# Sheet1.net
KiCad netlist of a schematic drawn in Altium Designer
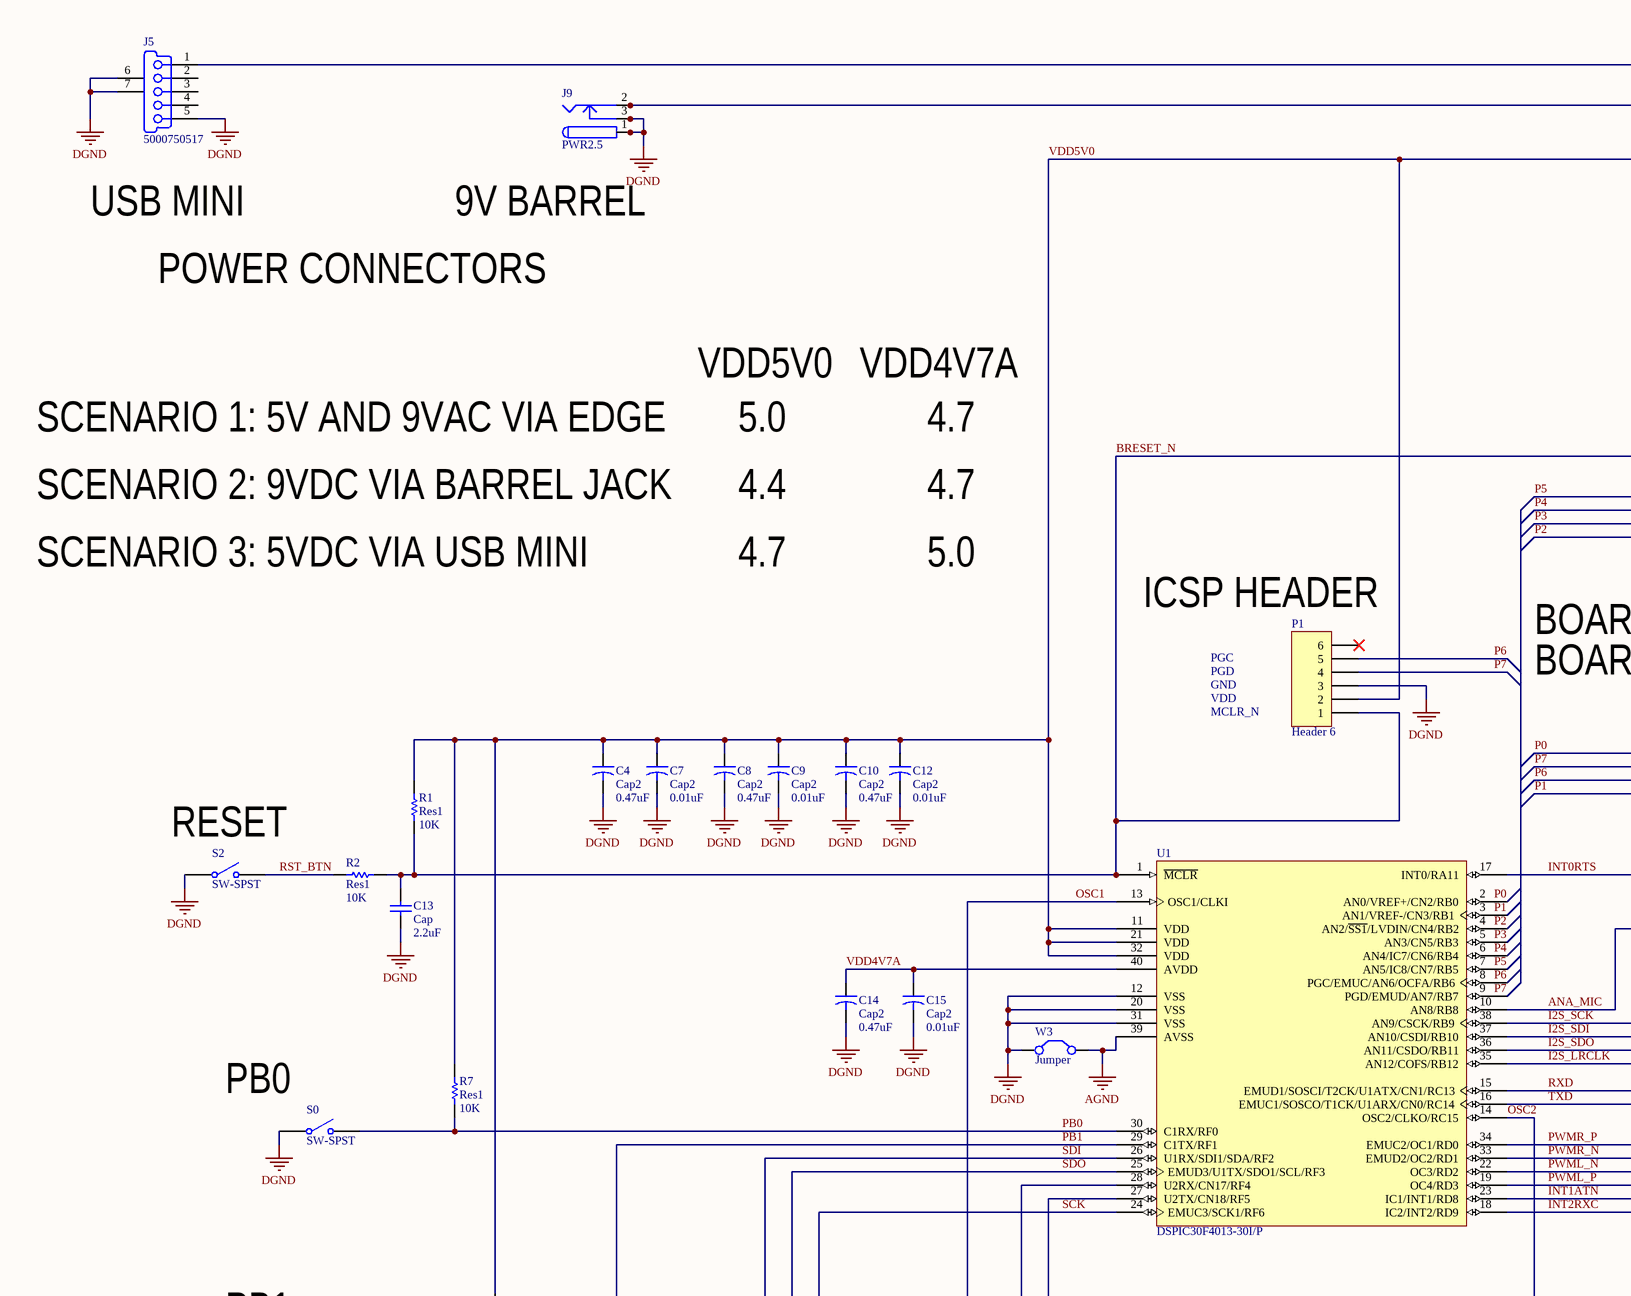
[diagram p0: Sheet1.SchDoc, top left]
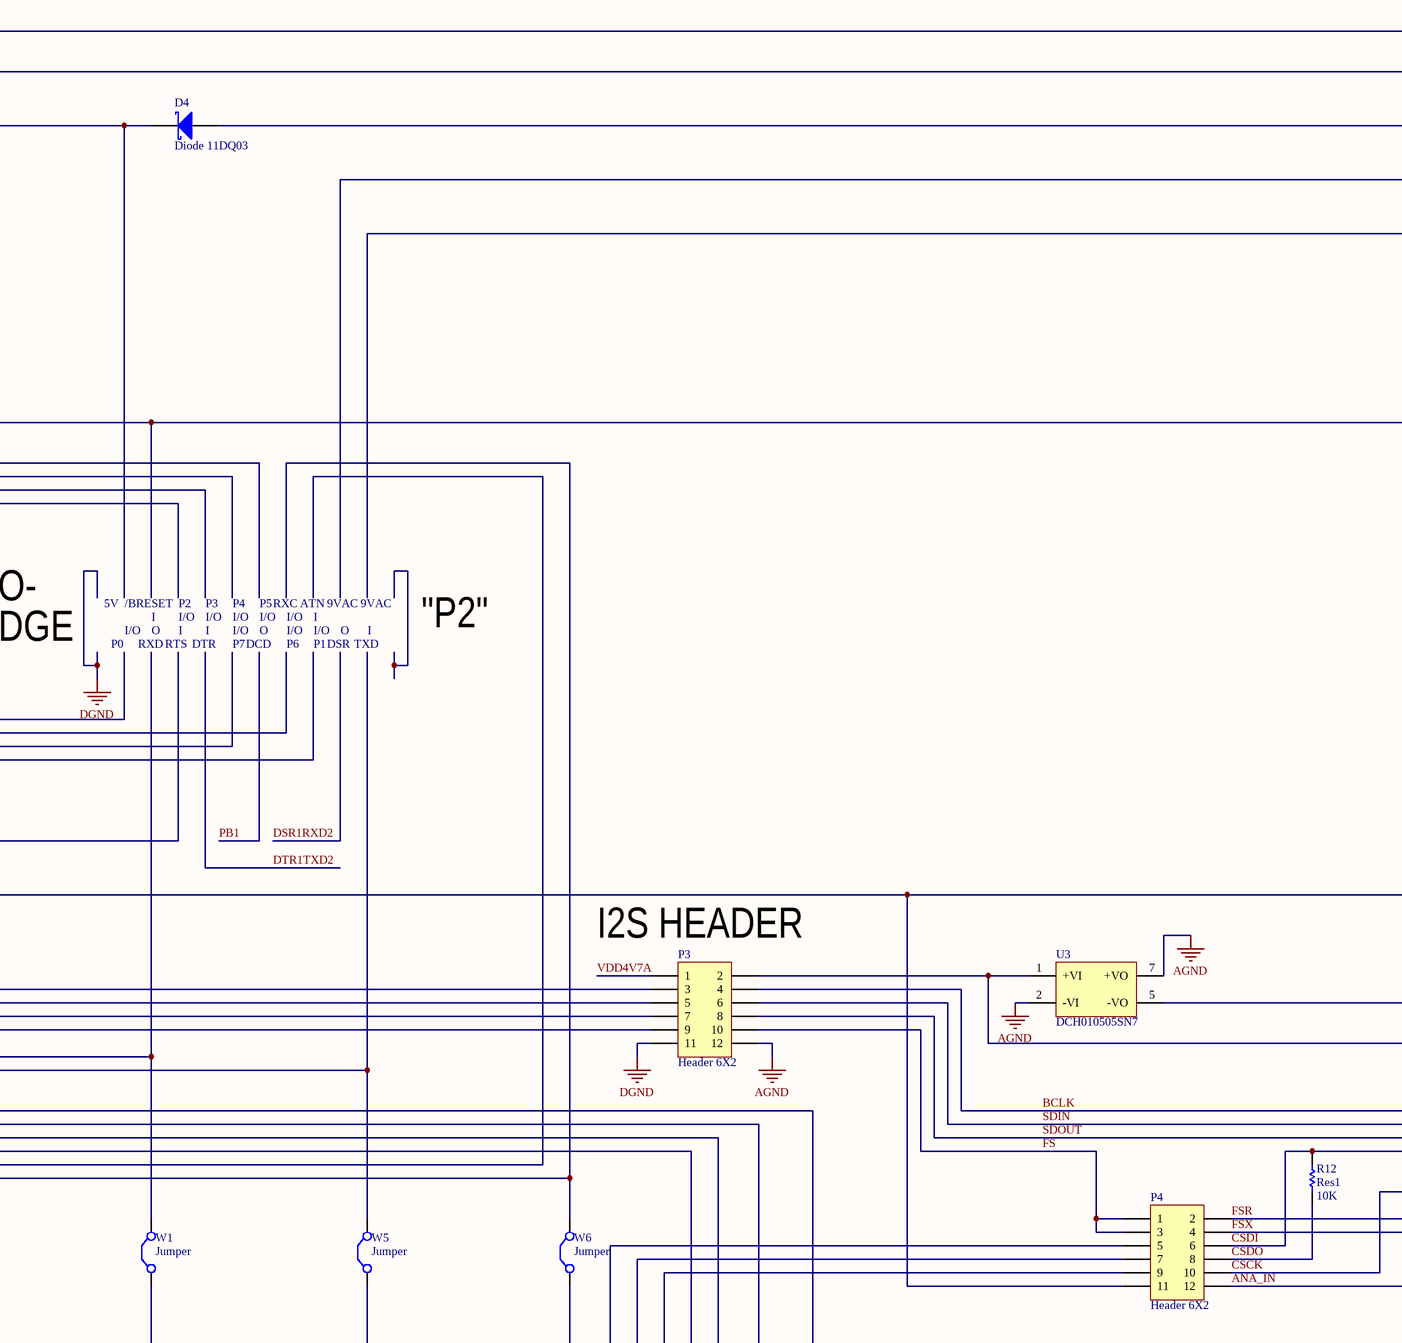
[diagram p1: Sheet1.SchDoc, top middle]
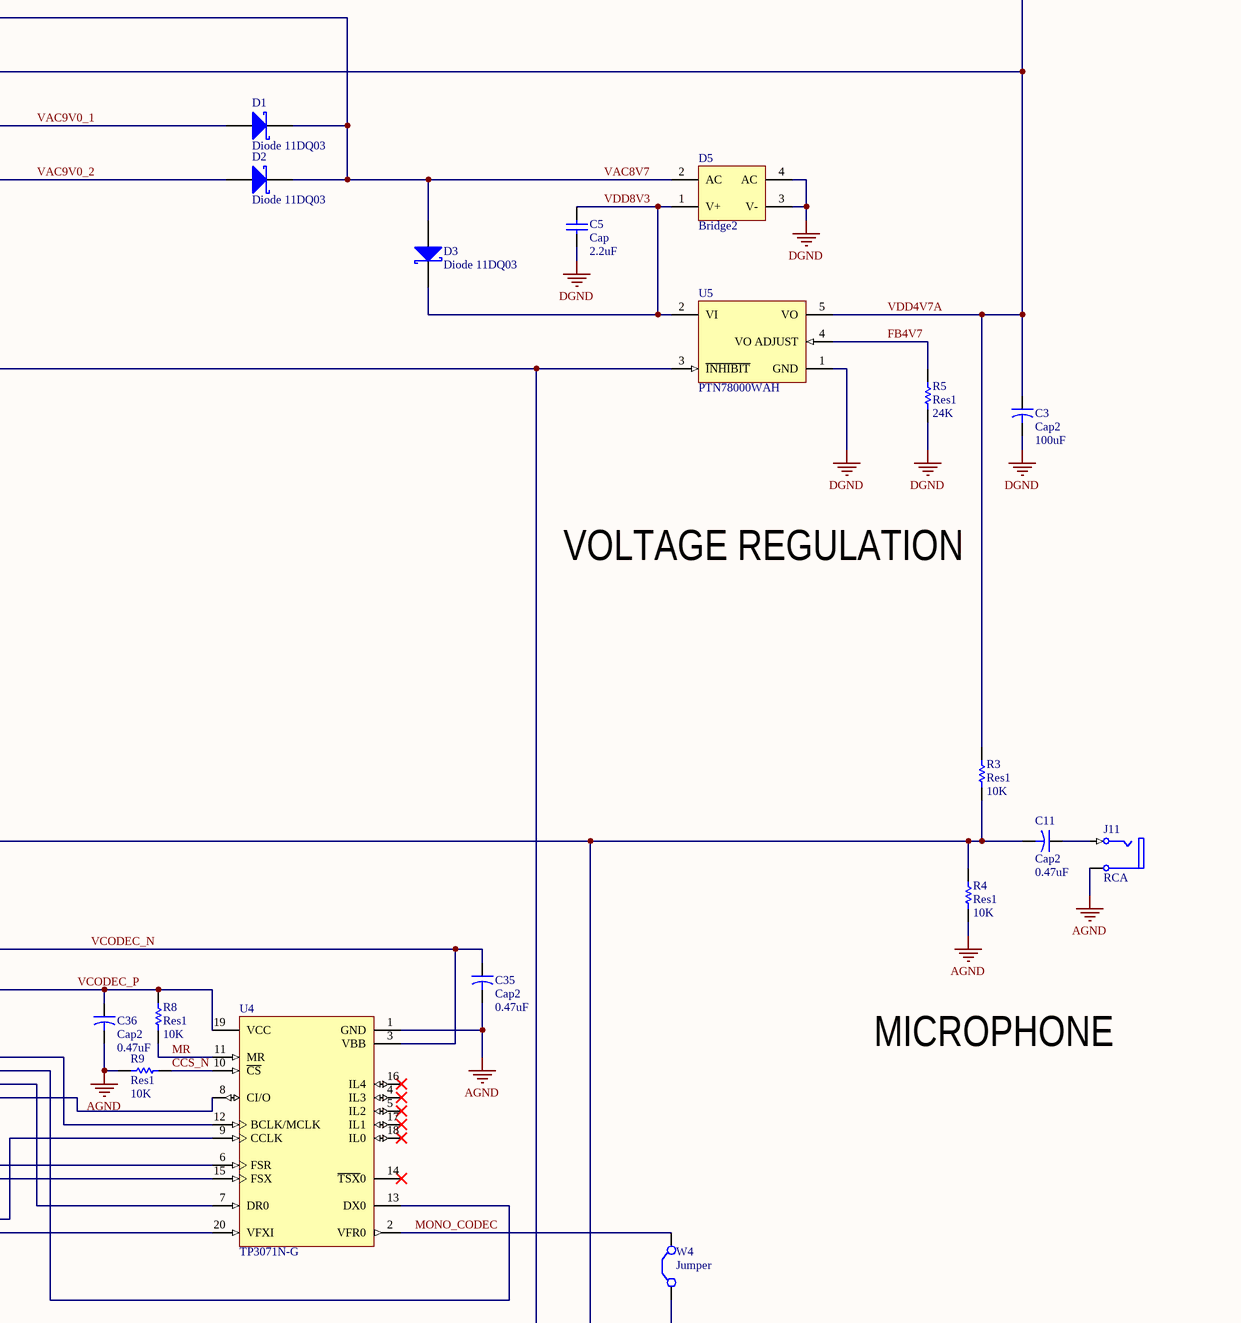
[diagram p2: Sheet1.SchDoc, top right]
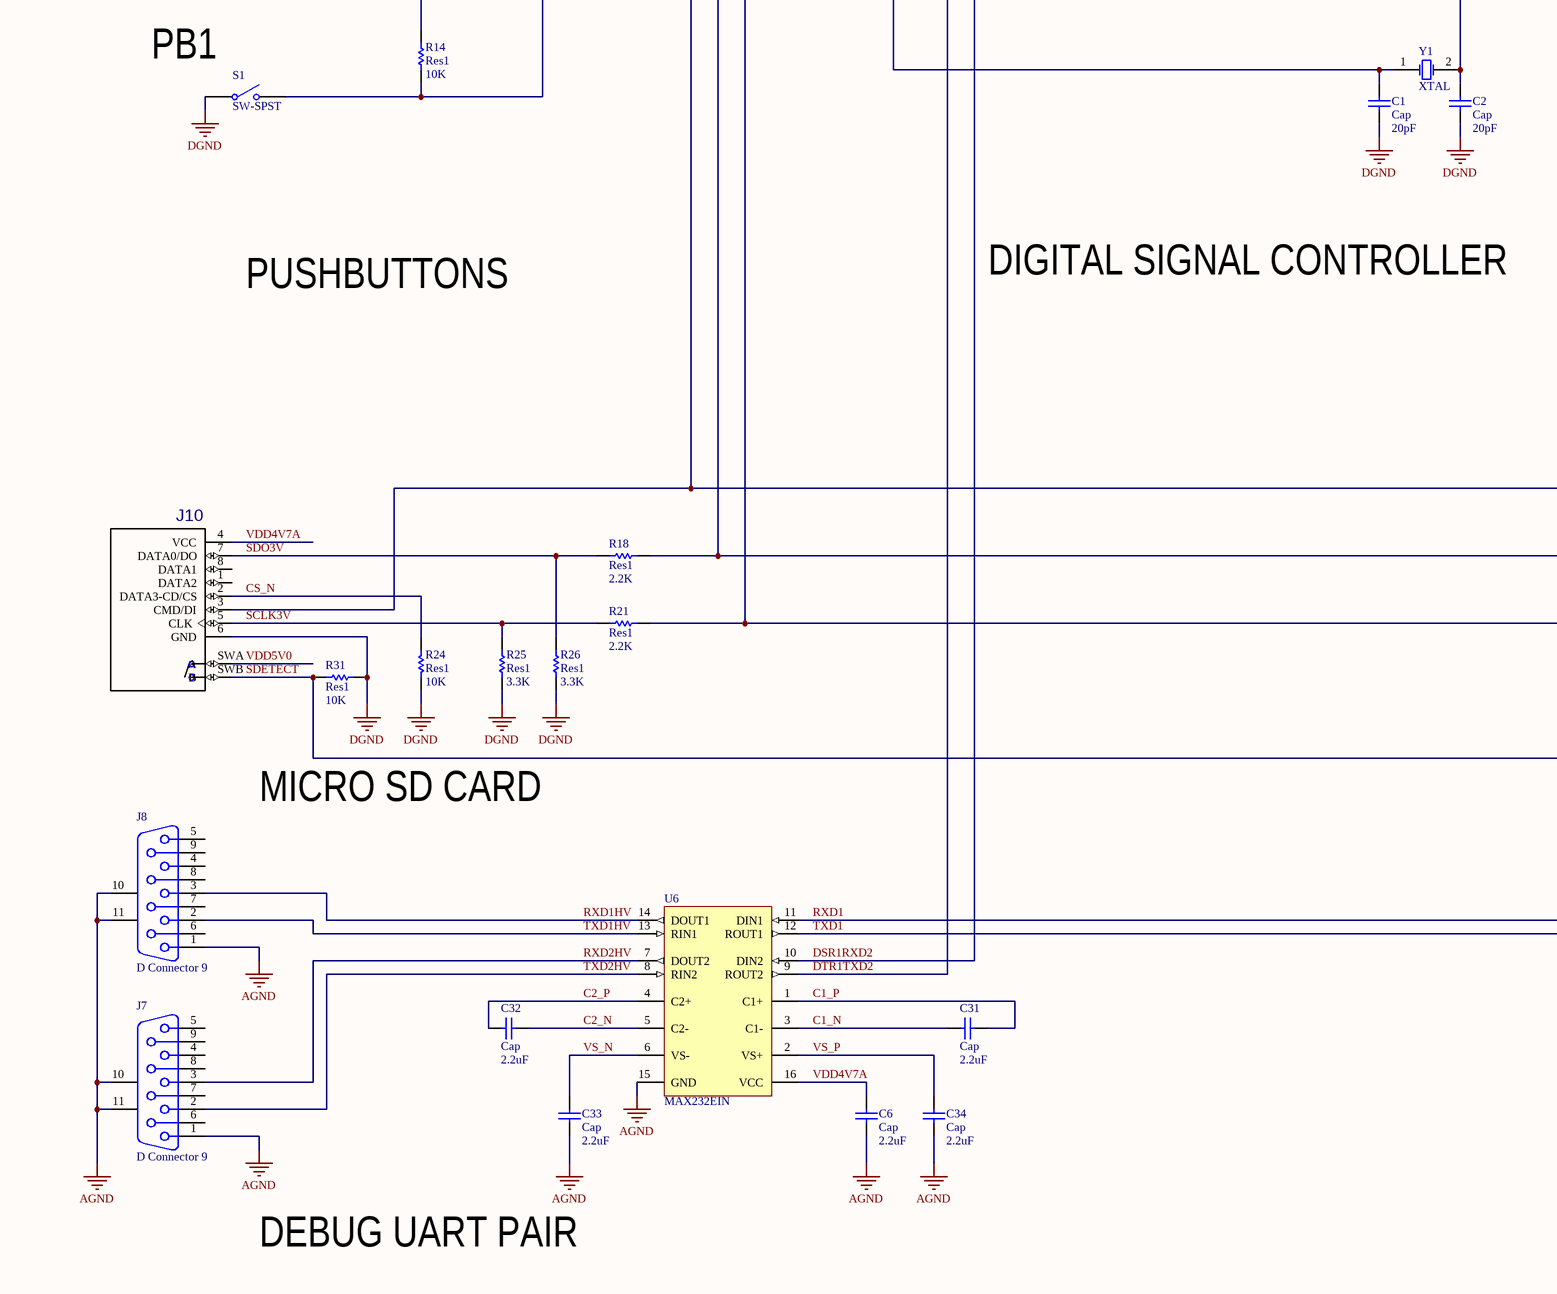
[diagram p3: Sheet1.SchDoc, bottom left]
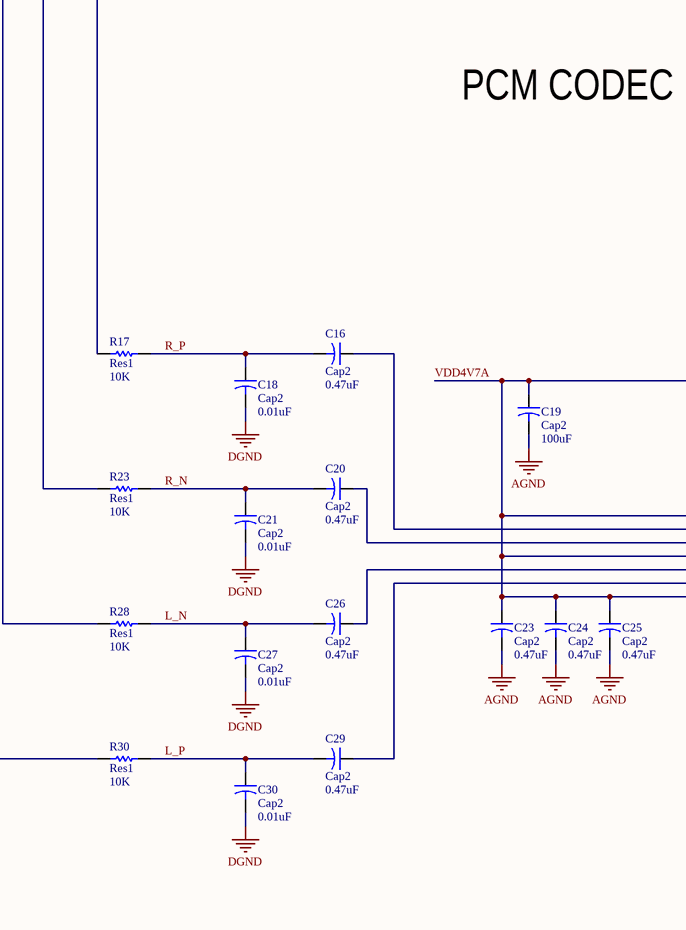
[diagram p4: Sheet1.SchDoc, bottom middle]
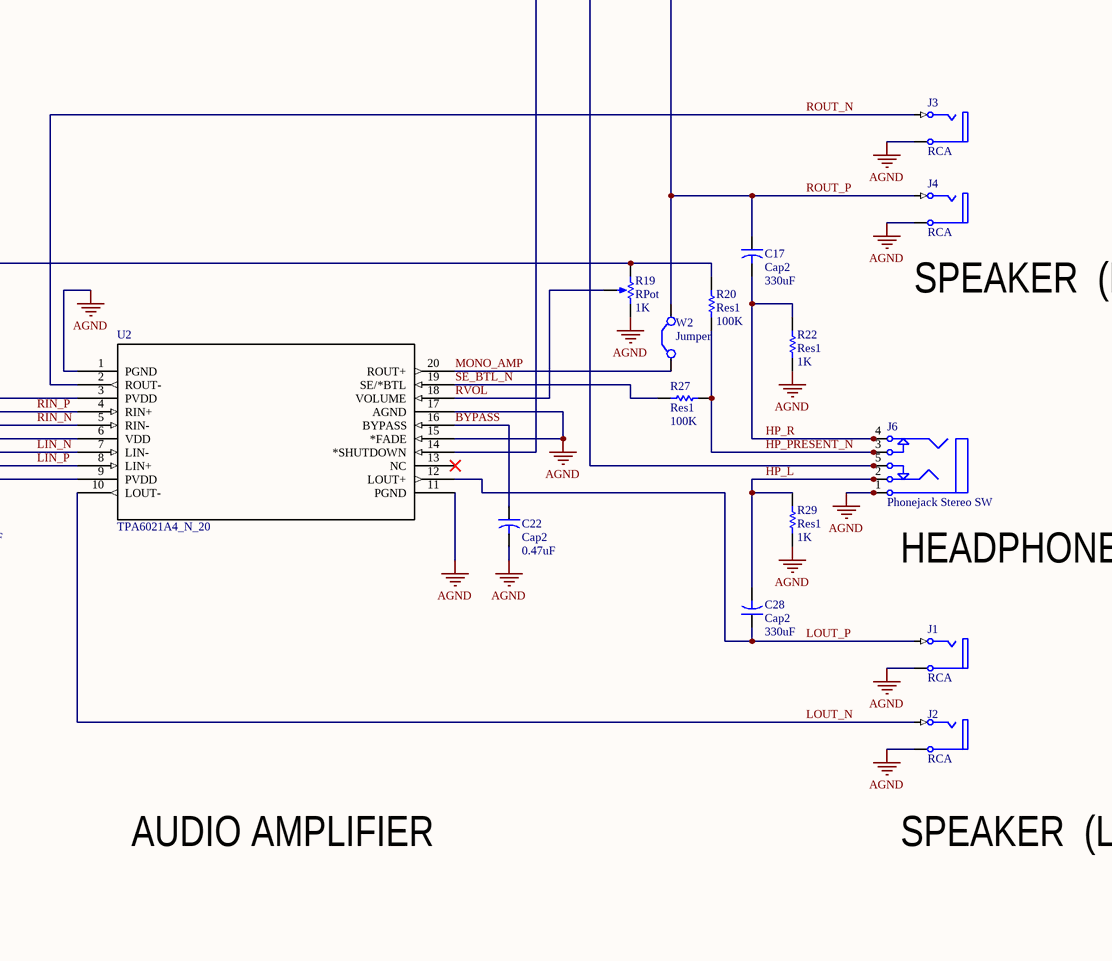
[diagram p5: Sheet1.SchDoc, bottom right]

(export (version "E")
  (design (tool "Eeschema 10.0.6"))
  (components
    (comp (ref "C1")
      (value "Cap")
      (footprint "RAD-0.3")
      (description "Capacitor")
      (fields (field (name "ALTIUM_VALUE") "20pF") (field (name "PUBLISHER") "Altium Limited"))
      (libsource (lib "Miscellaneous Devices") (part "Cap"))
    )
    (comp (ref "C2")
      (value "Cap")
      (footprint "RAD-0.3")
      (description "Capacitor")
      (fields (field (name "ALTIUM_VALUE") "20pF") (field (name "PUBLISHER") "Altium Limited"))
      (libsource (lib "Miscellaneous Devices") (part "Cap"))
    )
    (comp (ref "C3")
      (value "Cap2")
      (footprint "CAPR5-4X5")
      (description "Capacitor")
      (fields (field (name "ALTIUM_VALUE") "100uF") (field (name "PUBLISHER") "Altium Limited"))
      (libsource (lib "Miscellaneous Devices") (part "Cap2"))
    )
    (comp (ref "C4")
      (value "Cap2")
      (footprint "CAPR5-4X5")
      (description "Capacitor")
      (fields (field (name "ALTIUM_VALUE") "0.47uF") (field (name "PUBLISHER") "Altium Limited"))
      (libsource (lib "Miscellaneous Devices") (part "Cap2"))
    )
    (comp (ref "C5")
      (value "Cap")
      (footprint "RAD-0.3")
      (description "Capacitor")
      (fields (field (name "ALTIUM_VALUE") "2.2uF") (field (name "PUBLISHER") "Altium Limited"))
      (libsource (lib "Miscellaneous Devices") (part "Cap"))
    )
    (comp (ref "C6")
      (value "Cap")
      (footprint "RAD-0.3")
      (description "Capacitor")
      (fields (field (name "ALTIUM_VALUE") "2.2uF") (field (name "PUBLISHER") "Altium Limited"))
      (libsource (lib "Miscellaneous Devices") (part "Cap"))
    )
    (comp (ref "C7")
      (value "Cap2")
      (footprint "CAPR5-4X5")
      (description "Capacitor")
      (fields (field (name "ALTIUM_VALUE") "0.01uF") (field (name "PUBLISHER") "Altium Limited"))
      (libsource (lib "Miscellaneous Devices") (part "Cap2"))
    )
    (comp (ref "C8")
      (value "Cap2")
      (footprint "CAPR5-4X5")
      (description "Capacitor")
      (fields (field (name "ALTIUM_VALUE") "0.47uF") (field (name "PUBLISHER") "Altium Limited"))
      (libsource (lib "Miscellaneous Devices") (part "Cap2"))
    )
    (comp (ref "C9")
      (value "Cap2")
      (footprint "CAPR5-4X5")
      (description "Capacitor")
      (fields (field (name "ALTIUM_VALUE") "0.01uF") (field (name "PUBLISHER") "Altium Limited"))
      (libsource (lib "Miscellaneous Devices") (part "Cap2"))
    )
    (comp (ref "C10")
      (value "Cap2")
      (footprint "CAPR5-4X5")
      (description "Capacitor")
      (fields (field (name "ALTIUM_VALUE") "0.47uF") (field (name "PUBLISHER") "Altium Limited"))
      (libsource (lib "Miscellaneous Devices") (part "Cap2"))
    )
    (comp (ref "C11")
      (value "Cap2")
      (footprint "CAPR5-4X5")
      (description "Capacitor")
      (fields (field (name "ALTIUM_VALUE") "0.47uF") (field (name "PUBLISHER") "Altium Limited"))
      (libsource (lib "Miscellaneous Devices") (part "Cap2"))
    )
    (comp (ref "C12")
      (value "Cap2")
      (footprint "CAPR5-4X5")
      (description "Capacitor")
      (fields (field (name "ALTIUM_VALUE") "0.01uF") (field (name "PUBLISHER") "Altium Limited"))
      (libsource (lib "Miscellaneous Devices") (part "Cap2"))
    )
    (comp (ref "C13")
      (value "Cap")
      (footprint "RAD-0.3")
      (description "Capacitor")
      (fields (field (name "ALTIUM_VALUE") "2.2uF") (field (name "PUBLISHER") "Altium Limited"))
      (libsource (lib "Miscellaneous Devices") (part "Cap"))
    )
    (comp (ref "C14")
      (value "Cap2")
      (footprint "CAPR5-4X5")
      (description "Capacitor")
      (fields (field (name "ALTIUM_VALUE") "0.47uF") (field (name "PUBLISHER") "Altium Limited"))
      (libsource (lib "Miscellaneous Devices") (part "Cap2"))
    )
    (comp (ref "C15")
      (value "Cap2")
      (footprint "CAPR5-4X5")
      (description "Capacitor")
      (fields (field (name "ALTIUM_VALUE") "0.01uF") (field (name "PUBLISHER") "Altium Limited"))
      (libsource (lib "Miscellaneous Devices") (part "Cap2"))
    )
    (comp (ref "C16")
      (value "Cap2")
      (footprint "CAPR5-4X5")
      (description "Capacitor")
      (fields (field (name "ALTIUM_VALUE") "0.47uF") (field (name "PUBLISHER") "Altium Limited"))
      (libsource (lib "Miscellaneous Devices") (part "Cap2"))
    )
    (comp (ref "C17")
      (value "Cap2")
      (footprint "CAPR5-4X5")
      (description "Capacitor")
      (fields (field (name "ALTIUM_VALUE") "330uF") (field (name "PUBLISHER") "Altium Limited"))
      (libsource (lib "Miscellaneous Devices") (part "Cap2"))
    )
    (comp (ref "C18")
      (value "Cap2")
      (footprint "CAPR5-4X5")
      (description "Capacitor")
      (fields (field (name "ALTIUM_VALUE") "0.01uF") (field (name "PUBLISHER") "Altium Limited"))
      (libsource (lib "Miscellaneous Devices") (part "Cap2"))
    )
    (comp (ref "C19")
      (value "Cap2")
      (footprint "CAPR5-4X5")
      (description "Capacitor")
      (fields (field (name "ALTIUM_VALUE") "100uF") (field (name "PUBLISHER") "Altium Limited"))
      (libsource (lib "Miscellaneous Devices") (part "Cap2"))
    )
    (comp (ref "C20")
      (value "Cap2")
      (footprint "CAPR5-4X5")
      (description "Capacitor")
      (fields (field (name "ALTIUM_VALUE") "0.47uF") (field (name "PUBLISHER") "Altium Limited"))
      (libsource (lib "Miscellaneous Devices") (part "Cap2"))
    )
    (comp (ref "C21")
      (value "Cap2")
      (footprint "CAPR5-4X5")
      (description "Capacitor")
      (fields (field (name "ALTIUM_VALUE") "0.01uF") (field (name "PUBLISHER") "Altium Limited"))
      (libsource (lib "Miscellaneous Devices") (part "Cap2"))
    )
    (comp (ref "C22")
      (value "Cap2")
      (footprint "CAPR5-4X5")
      (description "Capacitor")
      (fields (field (name "ALTIUM_VALUE") "0.47uF") (field (name "PUBLISHER") "Altium Limited"))
      (libsource (lib "Miscellaneous Devices") (part "Cap2"))
    )
    (comp (ref "C23")
      (value "Cap2")
      (footprint "CAPR5-4X5")
      (description "Capacitor")
      (fields (field (name "ALTIUM_VALUE") "0.47uF") (field (name "PUBLISHER") "Altium Limited"))
      (libsource (lib "Miscellaneous Devices") (part "Cap2"))
    )
    (comp (ref "C24")
      (value "Cap2")
      (footprint "CAPR5-4X5")
      (description "Capacitor")
      (fields (field (name "ALTIUM_VALUE") "0.47uF") (field (name "PUBLISHER") "Altium Limited"))
      (libsource (lib "Miscellaneous Devices") (part "Cap2"))
    )
    (comp (ref "C25")
      (value "Cap2")
      (footprint "CAPR5-4X5")
      (description "Capacitor")
      (fields (field (name "ALTIUM_VALUE") "0.47uF") (field (name "PUBLISHER") "Altium Limited"))
      (libsource (lib "Miscellaneous Devices") (part "Cap2"))
    )
    (comp (ref "C26")
      (value "Cap2")
      (footprint "CAPR5-4X5")
      (description "Capacitor")
      (fields (field (name "ALTIUM_VALUE") "0.47uF") (field (name "PUBLISHER") "Altium Limited"))
      (libsource (lib "Miscellaneous Devices") (part "Cap2"))
    )
    (comp (ref "C27")
      (value "Cap2")
      (footprint "CAPR5-4X5")
      (description "Capacitor")
      (fields (field (name "ALTIUM_VALUE") "0.01uF") (field (name "PUBLISHER") "Altium Limited"))
      (libsource (lib "Miscellaneous Devices") (part "Cap2"))
    )
    (comp (ref "C28")
      (value "Cap2")
      (footprint "CAPR5-4X5")
      (description "Capacitor")
      (fields (field (name "ALTIUM_VALUE") "330uF") (field (name "PUBLISHER") "Altium Limited"))
      (libsource (lib "Miscellaneous Devices") (part "Cap2"))
    )
    (comp (ref "C29")
      (value "Cap2")
      (footprint "CAPR5-4X5")
      (description "Capacitor")
      (fields (field (name "ALTIUM_VALUE") "0.47uF") (field (name "PUBLISHER") "Altium Limited"))
      (libsource (lib "Miscellaneous Devices") (part "Cap2"))
    )
    (comp (ref "C30")
      (value "Cap2")
      (footprint "CAPR5-4X5")
      (description "Capacitor")
      (fields (field (name "ALTIUM_VALUE") "0.01uF") (field (name "PUBLISHER") "Altium Limited"))
      (libsource (lib "Miscellaneous Devices") (part "Cap2"))
    )
    (comp (ref "C31")
      (value "Cap")
      (footprint "RAD-0.3")
      (description "Capacitor")
      (fields (field (name "ALTIUM_VALUE") "2.2uF") (field (name "PUBLISHER") "Altium Limited"))
      (libsource (lib "Miscellaneous Devices") (part "Cap"))
    )
    (comp (ref "C32")
      (value "Cap")
      (footprint "RAD-0.3")
      (description "Capacitor")
      (fields (field (name "ALTIUM_VALUE") "2.2uF") (field (name "PUBLISHER") "Altium Limited"))
      (libsource (lib "Miscellaneous Devices") (part "Cap"))
    )
    (comp (ref "C33")
      (value "Cap")
      (footprint "RAD-0.3")
      (description "Capacitor")
      (fields (field (name "ALTIUM_VALUE") "2.2uF") (field (name "PUBLISHER") "Altium Limited"))
      (libsource (lib "Miscellaneous Devices") (part "Cap"))
    )
    (comp (ref "C34")
      (value "Cap")
      (footprint "RAD-0.3")
      (description "Capacitor")
      (fields (field (name "ALTIUM_VALUE") "2.2uF") (field (name "PUBLISHER") "Altium Limited"))
      (libsource (lib "Miscellaneous Devices") (part "Cap"))
    )
    (comp (ref "C35")
      (value "Cap2")
      (footprint "CAPR5-4X5")
      (description "Capacitor")
      (fields (field (name "ALTIUM_VALUE") "0.47uF") (field (name "PUBLISHER") "Altium Limited"))
      (libsource (lib "Miscellaneous Devices") (part "Cap2"))
    )
    (comp (ref "C36")
      (value "Cap2")
      (footprint "CAPR5-4X5")
      (description "Capacitor")
      (fields (field (name "ALTIUM_VALUE") "0.47uF") (field (name "PUBLISHER") "Altium Limited"))
      (libsource (lib "Miscellaneous Devices") (part "Cap2"))
    )
    (comp (ref "D1")
      (value "Diode 11DQ03")
      (footprint "DO-204AL")
      (description "Schottky Rectifier")
      (fields (field (name "PUBLISHER") "Altium Limited"))
      (libsource (lib "Miscellaneous Devices") (part "Diode 11DQ03"))
    )
    (comp (ref "D2")
      (value "Diode 11DQ03")
      (footprint "DO-204AL")
      (description "Schottky Rectifier")
      (fields (field (name "PUBLISHER") "Altium Limited"))
      (libsource (lib "Miscellaneous Devices") (part "Diode 11DQ03"))
    )
    (comp (ref "D3")
      (value "Diode 11DQ03")
      (footprint "DO-204AL")
      (description "Schottky Rectifier")
      (fields (field (name "PUBLISHER") "Altium Limited"))
      (libsource (lib "Miscellaneous Devices") (part "Diode 11DQ03"))
    )
    (comp (ref "D4")
      (value "Diode 11DQ03")
      (footprint "DO-204AL")
      (description "Schottky Rectifier")
      (fields (field (name "PUBLISHER") "Altium Limited"))
      (libsource (lib "Miscellaneous Devices") (part "Diode 11DQ03"))
    )
    (comp (ref "D5")
      (value "Bridge2")
      (footprint "D-46_6A")
      (description "Diode Bridge")
      (fields (field (name "PUBLISHER") "Altium Limited"))
      (libsource (lib "Miscellaneous Devices") (part "Bridge2"))
    )
    (comp (ref "J1")
      (value "RCA")
      (footprint "RCA/4.5-H2")
      (description "RCA Phono Jack, Right Angle, Thru-Hole, Snap-In")
      (fields (field (name "PUBLISHER") "Altium Limited"))
      (libsource (lib "Miscellaneous Connectors") (part "RCA"))
    )
    (comp (ref "J2")
      (value "RCA")
      (footprint "RCA/4.5-H2")
      (description "RCA Phono Jack, Right Angle, Thru-Hole, Snap-In")
      (fields (field (name "PUBLISHER") "Altium Limited"))
      (libsource (lib "Miscellaneous Connectors") (part "RCA"))
    )
    (comp (ref "J3")
      (value "RCA")
      (footprint "RCA/4.5-H2")
      (description "RCA Phono Jack, Right Angle, Thru-Hole, Snap-In")
      (fields (field (name "PUBLISHER") "Altium Limited"))
      (libsource (lib "Miscellaneous Connectors") (part "RCA"))
    )
    (comp (ref "J4")
      (value "RCA")
      (footprint "RCA/4.5-H2")
      (description "RCA Phono Jack, Right Angle, Thru-Hole, Snap-In")
      (fields (field (name "PUBLISHER") "Altium Limited"))
      (libsource (lib "Miscellaneous Connectors") (part "RCA"))
    )
    (comp (ref "J5")
      (value "5000750517")
      (footprint "5000750517")
      (fields (field (name "PUBLISHER") "Altium Limited"))
      (libsource (lib "Molex Serial Bus Mini USB") (part "5000750517"))
    )
    (comp (ref "J6")
      (value "Phonejack Stereo SW")
      (footprint "ST-3150-5N")
      (description "3-Conductor Jack with 2 break contacts (normals) and 2 auxiliary make contacts")
      (fields (field (name "PUBLISHER") "Altium Limited"))
      (libsource (lib "Miscellaneous Connectors") (part "Phonejack Stereo SW"))
    )
    (comp (ref "J7")
      (value "D Connector 9")
      (footprint "DSUB1.385-2H9")
      (description "Receptacle Assembly, 9 Position, Right Angle")
      (fields (field (name "PUBLISHER") "Altium Limited"))
      (libsource (lib "Miscellaneous Connectors") (part "D Connector 9"))
    )
    (comp (ref "J8")
      (value "D Connector 9")
      (footprint "DSUB1.385-2H9")
      (description "Receptacle Assembly, 9 Position, Right Angle")
      (fields (field (name "PUBLISHER") "Altium Limited"))
      (libsource (lib "Miscellaneous Connectors") (part "D Connector 9"))
    )
    (comp (ref "J9")
      (value "PWR2.5")
      (footprint "KLD-0202")
      (description "Low Voltage Power Supply Connector")
      (fields (field (name "PUBLISHER") "Altium Limited"))
      (libsource (lib "Miscellaneous Connectors") (part "PWR2.5"))
    )
    (comp (ref "J10")
      (value "DM3AT-SF-PEJM5")
      (footprint "HRS_DM3AT-SF-PEJM5_DM3AT-SF-PEJM5(Primary)")
      (fields (field (name "MF") "Hirose"))
      (libsource (lib "DM3AT-SF-PEJM5") (part "DM3AT-SF-PEJM5"))
    )
    (comp (ref "J11")
      (value "RCA")
      (footprint "RCA/4.5-H2")
      (description "RCA Phono Jack, Right Angle, Thru-Hole, Snap-In")
      (fields (field (name "PUBLISHER") "Altium Limited"))
      (libsource (lib "Miscellaneous Connectors") (part "RCA"))
    )
    (comp (ref "P1")
      (value "Header 6")
      (footprint "HDR1X6")
      (description "Header, 6-Pin")
      (fields (field (name "PUBLISHER") "Altium Limited"))
      (libsource (lib "Miscellaneous Connectors") (part "Header 6"))
    )
    (comp (ref "P3")
      (value "Header 6X2")
      (footprint "HDR2X6")
      (description "Header, 6-Pin, Dual row")
      (fields (field (name "PUBLISHER") "Altium Limited"))
      (libsource (lib "Miscellaneous Connectors") (part "Header 6X2"))
    )
    (comp (ref "P4")
      (value "Header 6X2")
      (footprint "HDR2X6")
      (description "Header, 6-Pin, Dual row")
      (fields (field (name "PUBLISHER") "Altium Limited"))
      (libsource (lib "Miscellaneous Connectors") (part "Header 6X2"))
    )
    (comp (ref "R1")
      (value "Res1")
      (footprint "AXIAL-0.3")
      (description "Resistor")
      (fields (field (name "ALTIUM_VALUE") "10K") (field (name "PUBLISHER") "Altium Limited"))
      (libsource (lib "Miscellaneous Devices") (part "Res1"))
    )
    (comp (ref "R2")
      (value "Res1")
      (footprint "AXIAL-0.3")
      (description "Resistor")
      (fields (field (name "ALTIUM_VALUE") "10K") (field (name "PUBLISHER") "Altium Limited"))
      (libsource (lib "Miscellaneous Devices") (part "Res1"))
    )
    (comp (ref "R3")
      (value "Res1")
      (footprint "AXIAL-0.3")
      (description "Resistor")
      (fields (field (name "ALTIUM_VALUE") "10K") (field (name "PUBLISHER") "Altium Limited"))
      (libsource (lib "Miscellaneous Devices") (part "Res1"))
    )
    (comp (ref "R4")
      (value "Res1")
      (footprint "AXIAL-0.3")
      (description "Resistor")
      (fields (field (name "ALTIUM_VALUE") "10K") (field (name "PUBLISHER") "Altium Limited"))
      (libsource (lib "Miscellaneous Devices") (part "Res1"))
    )
    (comp (ref "R5")
      (value "Res1")
      (footprint "AXIAL-0.3")
      (description "Resistor")
      (fields (field (name "ALTIUM_VALUE") "24K") (field (name "PUBLISHER") "Altium Limited"))
      (libsource (lib "Miscellaneous Devices") (part "Res1"))
    )
    (comp (ref "R7")
      (value "Res1")
      (footprint "AXIAL-0.3")
      (description "Resistor")
      (fields (field (name "ALTIUM_VALUE") "10K") (field (name "PUBLISHER") "Altium Limited"))
      (libsource (lib "Miscellaneous Devices") (part "Res1"))
    )
    (comp (ref "R8")
      (value "Res1")
      (footprint "AXIAL-0.3")
      (description "Resistor")
      (fields (field (name "ALTIUM_VALUE") "10K") (field (name "PUBLISHER") "Altium Limited"))
      (libsource (lib "Miscellaneous Devices") (part "Res1"))
    )
    (comp (ref "R9")
      (value "Res1")
      (footprint "AXIAL-0.3")
      (description "Resistor")
      (fields (field (name "ALTIUM_VALUE") "10K") (field (name "PUBLISHER") "Altium Limited"))
      (libsource (lib "Miscellaneous Devices") (part "Res1"))
    )
    (comp (ref "R12")
      (value "Res1")
      (footprint "AXIAL-0.3")
      (description "Resistor")
      (fields (field (name "ALTIUM_VALUE") "10K") (field (name "PUBLISHER") "Altium Limited"))
      (libsource (lib "Miscellaneous Devices") (part "Res1"))
    )
    (comp (ref "R14")
      (value "Res1")
      (footprint "AXIAL-0.3")
      (description "Resistor")
      (fields (field (name "ALTIUM_VALUE") "10K") (field (name "PUBLISHER") "Altium Limited"))
      (libsource (lib "Miscellaneous Devices") (part "Res1"))
    )
    (comp (ref "R17")
      (value "Res1")
      (footprint "AXIAL-0.3")
      (description "Resistor")
      (fields (field (name "ALTIUM_VALUE") "10K") (field (name "PUBLISHER") "Altium Limited"))
      (libsource (lib "Miscellaneous Devices") (part "Res1"))
    )
    (comp (ref "R18")
      (value "Res1")
      (footprint "AXIAL-0.3")
      (description "Resistor")
      (fields (field (name "ALTIUM_VALUE") "2.2K") (field (name "PUBLISHER") "Altium Limited"))
      (libsource (lib "Miscellaneous Devices") (part "Res1"))
    )
    (comp (ref "R19")
      (value "RPot")
      (footprint "VR5")
      (description "Potentiometer")
      (fields (field (name "ALTIUM_VALUE") "1K") (field (name "PUBLISHER") "Altium Limited"))
      (libsource (lib "Miscellaneous Devices") (part "RPot"))
    )
    (comp (ref "R20")
      (value "Res1")
      (footprint "AXIAL-0.3")
      (description "Resistor")
      (fields (field (name "ALTIUM_VALUE") "100K") (field (name "PUBLISHER") "Altium Limited"))
      (libsource (lib "Miscellaneous Devices") (part "Res1"))
    )
    (comp (ref "R21")
      (value "Res1")
      (footprint "AXIAL-0.3")
      (description "Resistor")
      (fields (field (name "ALTIUM_VALUE") "2.2K") (field (name "PUBLISHER") "Altium Limited"))
      (libsource (lib "Miscellaneous Devices") (part "Res1"))
    )
    (comp (ref "R22")
      (value "Res1")
      (footprint "AXIAL-0.3")
      (description "Resistor")
      (fields (field (name "ALTIUM_VALUE") "1K") (field (name "PUBLISHER") "Altium Limited"))
      (libsource (lib "Miscellaneous Devices") (part "Res1"))
    )
    (comp (ref "R23")
      (value "Res1")
      (footprint "AXIAL-0.3")
      (description "Resistor")
      (fields (field (name "ALTIUM_VALUE") "10K") (field (name "PUBLISHER") "Altium Limited"))
      (libsource (lib "Miscellaneous Devices") (part "Res1"))
    )
    (comp (ref "R24")
      (value "Res1")
      (footprint "AXIAL-0.3")
      (description "Resistor")
      (fields (field (name "ALTIUM_VALUE") "10K") (field (name "PUBLISHER") "Altium Limited"))
      (libsource (lib "Miscellaneous Devices") (part "Res1"))
    )
    (comp (ref "R25")
      (value "Res1")
      (footprint "AXIAL-0.3")
      (description "Resistor")
      (fields (field (name "ALTIUM_VALUE") "3.3K") (field (name "PUBLISHER") "Altium Limited"))
      (libsource (lib "Miscellaneous Devices") (part "Res1"))
    )
    (comp (ref "R26")
      (value "Res1")
      (footprint "AXIAL-0.3")
      (description "Resistor")
      (fields (field (name "ALTIUM_VALUE") "3.3K") (field (name "PUBLISHER") "Altium Limited"))
      (libsource (lib "Miscellaneous Devices") (part "Res1"))
    )
    (comp (ref "R27")
      (value "Res1")
      (footprint "AXIAL-0.3")
      (description "Resistor")
      (fields (field (name "ALTIUM_VALUE") "100K") (field (name "PUBLISHER") "Altium Limited"))
      (libsource (lib "Miscellaneous Devices") (part "Res1"))
    )
    (comp (ref "R28")
      (value "Res1")
      (footprint "AXIAL-0.3")
      (description "Resistor")
      (fields (field (name "ALTIUM_VALUE") "10K") (field (name "PUBLISHER") "Altium Limited"))
      (libsource (lib "Miscellaneous Devices") (part "Res1"))
    )
    (comp (ref "R29")
      (value "Res1")
      (footprint "AXIAL-0.3")
      (description "Resistor")
      (fields (field (name "ALTIUM_VALUE") "1K") (field (name "PUBLISHER") "Altium Limited"))
      (libsource (lib "Miscellaneous Devices") (part "Res1"))
    )
    (comp (ref "R30")
      (value "Res1")
      (footprint "AXIAL-0.3")
      (description "Resistor")
      (fields (field (name "ALTIUM_VALUE") "10K") (field (name "PUBLISHER") "Altium Limited"))
      (libsource (lib "Miscellaneous Devices") (part "Res1"))
    )
    (comp (ref "R31")
      (value "Res1")
      (footprint "AXIAL-0.3")
      (description "Resistor")
      (fields (field (name "ALTIUM_VALUE") "10K") (field (name "PUBLISHER") "Altium Limited"))
      (libsource (lib "Miscellaneous Devices") (part "Res1"))
    )
    (comp (ref "S0")
      (value "SW-SPST")
      (footprint "SPST-2")
      (description "Single-Pole, Single-Throw Switch")
      (fields (field (name "PUBLISHER") "Altium Limited"))
      (libsource (lib "Miscellaneous Devices") (part "SW-SPST"))
    )
    (comp (ref "S1")
      (value "SW-SPST")
      (footprint "SPST-2")
      (description "Single-Pole, Single-Throw Switch")
      (fields (field (name "PUBLISHER") "Altium Limited"))
      (libsource (lib "Miscellaneous Devices") (part "SW-SPST"))
    )
    (comp (ref "S2")
      (value "SW-SPST")
      (footprint "SPST-2")
      (description "Single-Pole, Single-Throw Switch")
      (fields (field (name "PUBLISHER") "Altium Limited"))
      (libsource (lib "Miscellaneous Devices") (part "SW-SPST"))
    )
    (comp (ref "U1")
      (value "DSPIC30F4013-30I/P")
      (footprint "PDIP600-P40")
      (fields (field (name "MANUFACTURER") "Microchip"))
      (libsource (lib "Microchip dsPIC30F") (part "DSPIC30F4013-30I/P"))
    )
    (comp (ref "U2")
      (value "TPA6021A4_N_20")
      (footprint "N20")
      (description "Imported")
      (fields
        (field (name "MANUFACTURER_PART_NUMBER") "tpa6021a4_n_20")
        (field (name "GENERIC_PART_NUMBER") "TPA6021A4")
      )
      (libsource (lib "TPA6021A") (part "TPA6021A4_N_20"))
    )
    (comp (ref "U3")
      (value "DCH010505SN7")
      (footprint "TI-EDJ4_V")
      (fields (field (name "MANUFACTURER") "Texas Instruments"))
      (libsource (lib "TI Power Management Power Modules") (part "DCH010505SN7"))
    )
    (comp (ref "U4")
      (value "TP3071N-G")
      (footprint "N20A")
      (description "COMBO II Programmable PCM CODEC/Filter, 20-pin MDIP")
      (fields (field (name "MANUFACTURER") "National Semiconductor"))
      (libsource (lib "National Semiconductor Analog") (part "TP3071N-G"))
    )
    (comp (ref "U5")
      (value "PTN78000WAH")
      (footprint "TI-EUS5_V")
      (fields (field (name "MANUFACTURER") "Texas Instruments"))
      (libsource (lib "TI Power Management Power Modules") (part "PTN78000WAH"))
    )
    (comp (ref "U6")
      (value "MAX232EIN")
      (footprint "TI-N16")
      (libsource (lib "Texas Instruments Interface RS-232") (part "MAX232EIN"))
    )
    (comp (ref "W1")
      (value "Jumper")
      (footprint "RAD-0.2")
      (description "Jumper Wire")
      (fields (field (name "PUBLISHER") "Altium Limited"))
      (libsource (lib "Miscellaneous Devices") (part "Jumper"))
    )
    (comp (ref "W2")
      (value "Jumper")
      (footprint "RAD-0.2")
      (description "Jumper Wire")
      (fields (field (name "PUBLISHER") "Altium Limited"))
      (libsource (lib "Miscellaneous Devices") (part "Jumper"))
    )
    (comp (ref "W3")
      (value "Jumper")
      (footprint "RAD-0.2")
      (description "Jumper Wire")
      (fields (field (name "PUBLISHER") "Altium Limited"))
      (libsource (lib "Miscellaneous Devices") (part "Jumper"))
    )
    (comp (ref "W4")
      (value "Jumper")
      (footprint "RAD-0.2")
      (description "Jumper Wire")
      (fields (field (name "PUBLISHER") "Altium Limited"))
      (libsource (lib "Miscellaneous Devices") (part "Jumper"))
    )
    (comp (ref "W5")
      (value "Jumper")
      (footprint "RAD-0.2")
      (description "Jumper Wire")
      (fields (field (name "PUBLISHER") "Altium Limited"))
      (libsource (lib "Miscellaneous Devices") (part "Jumper"))
    )
    (comp (ref "W6")
      (value "Jumper")
      (footprint "RAD-0.2")
      (description "Jumper Wire")
      (fields (field (name "PUBLISHER") "Altium Limited"))
      (libsource (lib "Miscellaneous Devices") (part "Jumper"))
    )
    (comp (ref "Y1")
      (value "XTAL")
      (footprint "R38")
      (description "Crystal Oscillator")
      (fields (field (name "PUBLISHER") "Altium Limited"))
      (libsource (lib "Miscellaneous Devices") (part "XTAL"))
    )
  )
  (nets
    (net (code "1") (name "/ANA_IN") (class "Default")
      (node (ref "P4") (pin "12") (pinfunction "12_12") (pintype "passive"))
      (node (ref "U4") (pin "20") (pinfunction "VFXI_20") (pintype "input"))
    )
    (net (code "2") (name "/ANA_MIC") (class "Default")
      (node (ref "C11") (pin "2") (pinfunction "2_2") (pintype "passive"))
      (node (ref "J6") (pin "5") (pinfunction "5_5") (pintype "passive"))
      (node (ref "J6") (pin "5A") (pinfunction "5A_5A") (pintype "passive"))
      (node (ref "J6") (pin "5B") (pinfunction "5B_5B") (pintype "passive"))
      (node (ref "P4") (pin "11") (pinfunction "11_11") (pintype "passive"))
      (node (ref "R3") (pin "2") (pinfunction "2_2") (pintype "passive"))
      (node (ref "R4") (pin "1") (pinfunction "1_1") (pintype "passive"))
      (node (ref "U1") (pin "10") (pinfunction "AN8/RB8_10") (pintype "bidirectional"))
    )
    (net (code "3") (name "/BCLK") (class "Default")
      (node (ref "P3") (pin "4") (pinfunction "4_4") (pintype "passive"))
      (node (ref "U4") (pin "12") (pinfunction "BCLK/MCLK_12") (pintype "input"))
    )
    (net (code "4") (name "/BRESET_N") (class "Default")
      (node (ref "C13") (pin "1") (pinfunction "1_1") (pintype "passive"))
      (node (ref "P1") (pin "1") (pinfunction "1_1") (pintype "passive"))
      (node (ref "R1") (pin "1") (pinfunction "1_1") (pintype "passive"))
      (node (ref "R2") (pin "1") (pinfunction "1_1") (pintype "passive"))
      (node (ref "U1") (pin "1") (pinfunction "~{MCLR}_1") (pintype "input"))
      (node (ref "U2") (pin "14") (pinfunction "*SHUTDOWN_14") (pintype "input"))
      (node (ref "U5") (pin "3") (pinfunction "~{INHIBIT}_3") (pintype "input"))
    )
    (net (code "5") (name "/BYPASS") (class "Default")
      (node (ref "C22") (pin "1") (pinfunction "1_1") (pintype "passive"))
      (node (ref "U2") (pin "16") (pinfunction "BYPASS_16") (pintype "input"))
    )
    (net (code "6") (name "/C1_N") (class "Default")
      (node (ref "C31") (pin "1") (pinfunction "1_1") (pintype "passive"))
      (node (ref "U6") (pin "3") (pinfunction "C1-_3") (pintype "passive"))
    )
    (net (code "7") (name "/C1_P") (class "Default")
      (node (ref "C31") (pin "2") (pinfunction "2_2") (pintype "passive"))
      (node (ref "U6") (pin "1") (pinfunction "C1+_1") (pintype "passive"))
    )
    (net (code "8") (name "/C2_N") (class "Default")
      (node (ref "C32") (pin "2") (pinfunction "2_2") (pintype "passive"))
      (node (ref "U6") (pin "5") (pinfunction "C2-_5") (pintype "passive"))
    )
    (net (code "9") (name "/C2_P") (class "Default")
      (node (ref "C32") (pin "1") (pinfunction "1_1") (pintype "passive"))
      (node (ref "U6") (pin "4") (pinfunction "C2+_4") (pintype "passive"))
    )
    (net (code "10") (name "/CCS_N") (class "Default")
      (node (ref "R9") (pin "1") (pinfunction "1_1") (pintype "passive"))
      (node (ref "U4") (pin "10") (pinfunction "~{CS}_10") (pintype "input"))
    )
    (net (code "11") (name "/CSCK") (class "Default")
      (node (ref "P4") (pin "10") (pinfunction "10_10") (pintype "passive"))
      (node (ref "U4") (pin "9") (pinfunction "CCLK_9") (pintype "input"))
    )
    (net (code "12") (name "/CSDI") (class "Default")
      (node (ref "P4") (pin "6") (pinfunction "6_6") (pintype "passive"))
      (node (ref "R12") (pin "2") (pinfunction "2_2") (pintype "passive"))
      (node (ref "U4") (pin "8") (pinfunction "CI/O_8") (pintype "bidirectional"))
    )
    (net (code "13") (name "/CSDO") (class "Default")
      (node (ref "P4") (pin "8") (pinfunction "8_8") (pintype "passive"))
      (node (ref "R12") (pin "1") (pinfunction "1_1") (pintype "passive"))
    )
    (net (code "14") (name "/CS_N") (class "Default")
      (node (ref "J10") (pin "2") (pinfunction "DATA3-CD/CS_2") (pintype "bidirectional"))
      (node (ref "R24") (pin "2") (pinfunction "2_2") (pintype "passive"))
    )
    (net (code "15") (name "/DSR1RXD2") (class "Default")
      (node (ref "U1") (pin "27") (pinfunction "U2TX/CN18/RF5_27") (pintype "bidirectional"))
      (node (ref "U6") (pin "10") (pinfunction "DIN2_10") (pintype "input"))
    )
    (net (code "16") (name "/DTR1TXD2") (class "Default")
      (node (ref "U1") (pin "28") (pinfunction "U2RX/CN17/RF4_28") (pintype "bidirectional"))
      (node (ref "U6") (pin "9") (pinfunction "ROUT2_9") (pintype "output"))
    )
    (net (code "17") (name "/FB4V7") (class "Default")
      (node (ref "R5") (pin "2") (pinfunction "2_2") (pintype "passive"))
      (node (ref "U5") (pin "4") (pinfunction "VO_ADJUST_4") (pintype "input"))
    )
    (net (code "18") (name "/FS") (class "Default")
      (node (ref "P3") (pin "10") (pinfunction "10_10") (pintype "passive"))
      (node (ref "P4") (pin "1") (pinfunction "1_1") (pintype "passive"))
      (node (ref "P4") (pin "3") (pinfunction "3_3") (pintype "passive"))
    )
    (net (code "19") (name "/FSR") (class "Default")
      (node (ref "P4") (pin "2") (pinfunction "2_2") (pintype "passive"))
      (node (ref "U4") (pin "6") (pinfunction "FSR_6") (pintype "input"))
    )
    (net (code "20") (name "/FSX") (class "Default")
      (node (ref "P4") (pin "4") (pinfunction "4_4") (pintype "passive"))
      (node (ref "U4") (pin "15") (pinfunction "FSX_15") (pintype "input"))
    )
    (net (code "21") (name "/HP_L") (class "Default")
      (node (ref "C28") (pin "2") (pinfunction "2_2") (pintype "passive"))
      (node (ref "J6") (pin "2") (pinfunction "2_2") (pintype "passive"))
      (node (ref "J6") (pin "2A") (pinfunction "2A_2A") (pintype "passive"))
      (node (ref "J6") (pin "2B") (pinfunction "2B_2B") (pintype "passive"))
      (node (ref "R29") (pin "2") (pinfunction "2_2") (pintype "passive"))
    )
    (net (code "22") (name "/HP_PRESENT_N") (class "Default")
      (node (ref "J6") (pin "3") (pinfunction "3_3") (pintype "passive"))
      (node (ref "J6") (pin "3A") (pinfunction "3A_3A") (pintype "passive"))
      (node (ref "J6") (pin "3B") (pinfunction "3B_3B") (pintype "passive"))
      (node (ref "R20") (pin "1") (pinfunction "1_1") (pintype "passive"))
      (node (ref "R27") (pin "1") (pinfunction "1_1") (pintype "passive"))
    )
    (net (code "23") (name "/HP_R") (class "Default")
      (node (ref "C17") (pin "2") (pinfunction "2_2") (pintype "passive"))
      (node (ref "J6") (pin "4") (pinfunction "4_4") (pintype "passive"))
      (node (ref "J6") (pin "4A") (pinfunction "4A_4A") (pintype "passive"))
      (node (ref "J6") (pin "4B") (pinfunction "4B_4B") (pintype "passive"))
      (node (ref "R22") (pin "2") (pinfunction "2_2") (pintype "passive"))
    )
    (net (code "24") (name "/I2S_LRCLK") (class "Default")
      (node (ref "P3") (pin "9") (pinfunction "9_9") (pintype "passive"))
      (node (ref "U1") (pin "35") (pinfunction "AN12/COFS/RB12_35") (pintype "bidirectional"))
    )
    (net (code "25") (name "/I2S_SCK") (class "Default")
      (node (ref "P3") (pin "3") (pinfunction "3_3") (pintype "passive"))
      (node (ref "U1") (pin "38") (pinfunction "AN9/CSCK/RB9_38") (pintype "bidirectional"))
    )
    (net (code "26") (name "/I2S_SDI") (class "Default")
      (node (ref "P3") (pin "5") (pinfunction "5_5") (pintype "passive"))
      (node (ref "U1") (pin "37") (pinfunction "AN10/CSDI/RB10_37") (pintype "bidirectional"))
    )
    (net (code "27") (name "/I2S_SDO") (class "Default")
      (node (ref "P3") (pin "7") (pinfunction "7_7") (pintype "passive"))
      (node (ref "U1") (pin "36") (pinfunction "AN11/CSDO/RB11_36") (pintype "bidirectional"))
    )
    (net (code "28") (name "/INT0RTS") (class "Default")
      (node (ref "U1") (pin "17") (pinfunction "INT0/RA11_17") (pintype "bidirectional"))
    )
    (net (code "29") (name "/INT1ATN") (class "Default")
      (node (ref "U1") (pin "23") (pinfunction "IC1/INT1/RD8_23") (pintype "bidirectional"))
    )
    (net (code "30") (name "/INT2RXC") (class "Default")
      (node (ref "U1") (pin "18") (pinfunction "IC2/INT2/RD9_18") (pintype "bidirectional"))
      (node (ref "W6") (pin "2") (pinfunction "C2_2") (pintype "passive"))
    )
    (net (code "31") (name "/LIN_N") (class "Default")
      (node (ref "C26") (pin "1") (pinfunction "1_1") (pintype "passive"))
      (node (ref "U2") (pin "7") (pinfunction "LIN-_7") (pintype "input"))
    )
    (net (code "32") (name "/LIN_P") (class "Default")
      (node (ref "C29") (pin "1") (pinfunction "1_1") (pintype "passive"))
      (node (ref "U2") (pin "8") (pinfunction "LIN+_8") (pintype "input"))
    )
    (net (code "33") (name "/LOUT_N") (class "Default")
      (node (ref "J2") (pin "2B") (pinfunction "Signal_2B") (pintype "input"))
      (node (ref "U2") (pin "10") (pinfunction "LOUT-_10") (pintype "output"))
    )
    (net (code "34") (name "/LOUT_P") (class "Default")
      (node (ref "C28") (pin "1") (pinfunction "1_1") (pintype "passive"))
      (node (ref "J1") (pin "2B") (pinfunction "Signal_2B") (pintype "input"))
      (node (ref "U2") (pin "12") (pinfunction "LOUT+_12") (pintype "output"))
    )
    (net (code "35") (name "/L_N") (class "Default")
      (node (ref "C26") (pin "2") (pinfunction "2_2") (pintype "passive"))
      (node (ref "C27") (pin "1") (pinfunction "1_1") (pintype "passive"))
      (node (ref "R28") (pin "2") (pinfunction "2_2") (pintype "passive"))
    )
    (net (code "36") (name "/L_P") (class "Default")
      (node (ref "C29") (pin "2") (pinfunction "2_2") (pintype "passive"))
      (node (ref "C30") (pin "1") (pinfunction "1_1") (pintype "passive"))
      (node (ref "R30") (pin "2") (pinfunction "2_2") (pintype "passive"))
    )
    (net (code "37") (name "/MONO_AMP") (class "Default")
      (node (ref "U2") (pin "20") (pinfunction "ROUT+_20") (pintype "output"))
      (node (ref "W2") (pin "1") (pinfunction "C1_1") (pintype "passive"))
    )
    (net (code "38") (name "/MONO_CODEC") (class "Default")
      (node (ref "U4") (pin "2") (pinfunction "VFR0_2") (pintype "output"))
      (node (ref "W4") (pin "2") (pinfunction "C2_2") (pintype "passive"))
    )
    (net (code "39") (name "/MR") (class "Default")
      (node (ref "R8") (pin "2") (pinfunction "2_2") (pintype "passive"))
      (node (ref "U4") (pin "11") (pinfunction "MR_11") (pintype "input"))
    )
    (net (code "40") (name "/OSC1") (class "Default")
      (node (ref "C1") (pin "2") (pinfunction "2_2") (pintype "passive"))
      (node (ref "U1") (pin "13") (pinfunction "OSC1/CLKI_13") (pintype "input"))
      (node (ref "Y1") (pin "1") (pinfunction "OSC1_1") (pintype "passive"))
    )
    (net (code "41") (name "/OSC2") (class "Default")
      (node (ref "C2") (pin "2") (pinfunction "2_2") (pintype "passive"))
      (node (ref "U1") (pin "14") (pinfunction "OSC2/CLKO/RC15_14") (pintype "bidirectional"))
      (node (ref "Y1") (pin "2") (pinfunction "OSC2_2") (pintype "passive"))
    )
    (net (code "48") (name "/P6") (class "Default")
      (node (ref "P1") (pin "5") (pinfunction "5_5") (pintype "passive"))
    )
    (net (code "49") (name "/P7") (class "Default")
      (node (ref "P1") (pin "4") (pinfunction "4_4") (pintype "passive"))
    )
    (net (code "50") (name "/PB0") (class "Default")
      (node (ref "R7") (pin "1") (pinfunction "1_1") (pintype "passive"))
      (node (ref "S0") (pin "2") (pinfunction "NO_2") (pintype "passive"))
      (node (ref "U1") (pin "30") (pinfunction "C1RX/RF0_30") (pintype "bidirectional"))
    )
    (net (code "51") (name "/PB1") (class "Default")
      (node (ref "R14") (pin "1") (pinfunction "1_1") (pintype "passive"))
      (node (ref "S1") (pin "2") (pinfunction "NO_2") (pintype "passive"))
      (node (ref "U1") (pin "29") (pinfunction "C1TX/RF1_29") (pintype "bidirectional"))
    )
    (net (code "52") (name "/PWML_N") (class "Default")
      (node (ref "R28") (pin "1") (pinfunction "1_1") (pintype "passive"))
      (node (ref "U1") (pin "22") (pinfunction "OC3/RD2_22") (pintype "bidirectional"))
    )
    (net (code "53") (name "/PWML_P") (class "Default")
      (node (ref "R30") (pin "1") (pinfunction "1_1") (pintype "passive"))
      (node (ref "U1") (pin "19") (pinfunction "OC4/RD3_19") (pintype "bidirectional"))
    )
    (net (code "54") (name "/PWMR_N") (class "Default")
      (node (ref "R23") (pin "1") (pinfunction "1_1") (pintype "passive"))
      (node (ref "U1") (pin "33") (pinfunction "EMUD2/OC2/RD1_33") (pintype "bidirectional"))
    )
    (net (code "55") (name "/PWMR_P") (class "Default")
      (node (ref "R17") (pin "1") (pinfunction "1_1") (pintype "passive"))
      (node (ref "U1") (pin "34") (pinfunction "EMUC2/OC1/RD0_34") (pintype "bidirectional"))
    )
    (net (code "56") (name "/RIN_N") (class "Default")
      (node (ref "C20") (pin "1") (pinfunction "1_1") (pintype "passive"))
      (node (ref "U2") (pin "5") (pinfunction "RIN-_5") (pintype "input"))
    )
    (net (code "57") (name "/RIN_P") (class "Default")
      (node (ref "C16") (pin "1") (pinfunction "1_1") (pintype "passive"))
      (node (ref "U2") (pin "4") (pinfunction "RIN+_4") (pintype "input"))
    )
    (net (code "58") (name "/ROUT_N") (class "Default")
      (node (ref "J3") (pin "2B") (pinfunction "Signal_2B") (pintype "input"))
      (node (ref "U2") (pin "2") (pinfunction "ROUT-_2") (pintype "output"))
    )
    (net (code "59") (name "/ROUT_P") (class "Default")
      (node (ref "C17") (pin "1") (pinfunction "1_1") (pintype "passive"))
      (node (ref "J4") (pin "2B") (pinfunction "Signal_2B") (pintype "input"))
      (node (ref "W2") (pin "2") (pinfunction "C2_2") (pintype "passive"))
      (node (ref "W4") (pin "1") (pinfunction "C1_1") (pintype "passive"))
    )
    (net (code "60") (name "/RST_BTN") (class "Default")
      (node (ref "R2") (pin "2") (pinfunction "2_2") (pintype "passive"))
      (node (ref "S2") (pin "2") (pinfunction "NO_2") (pintype "passive"))
    )
    (net (code "61") (name "/RVOL") (class "Default")
      (node (ref "R19") (pin "3") (pinfunction "TAP_3") (pintype "passive"))
      (node (ref "U2") (pin "18") (pinfunction "VOLUME_18") (pintype "input"))
    )
    (net (code "62") (name "/RXD") (class "Default")
      (node (ref "U1") (pin "15") (pinfunction "EMUD1/SOSCI/T2CK/U1ATX/CN1/RC13_15") (pintype "bidirectional"))
      (node (ref "W1") (pin "2") (pinfunction "C2_2") (pintype "passive"))
    )
    (net (code "63") (name "/RXD1") (class "Default")
      (node (ref "U6") (pin "11") (pinfunction "DIN1_11") (pintype "input"))
      (node (ref "W1") (pin "1") (pinfunction "C1_1") (pintype "passive"))
    )
    (net (code "64") (name "/RXD1HV") (class "Default")
      (node (ref "J8") (pin "3") (pinfunction "3_3") (pintype "passive"))
      (node (ref "U6") (pin "14") (pinfunction "DOUT1_14") (pintype "output"))
    )
    (net (code "65") (name "/RXD2HV") (class "Default")
      (node (ref "J7") (pin "3") (pinfunction "3_3") (pintype "passive"))
      (node (ref "U6") (pin "7") (pinfunction "DOUT2_7") (pintype "output"))
    )
    (net (code "66") (name "/R_N") (class "Default")
      (node (ref "C20") (pin "2") (pinfunction "2_2") (pintype "passive"))
      (node (ref "C21") (pin "1") (pinfunction "1_1") (pintype "passive"))
      (node (ref "R23") (pin "2") (pinfunction "2_2") (pintype "passive"))
    )
    (net (code "67") (name "/R_P") (class "Default")
      (node (ref "C16") (pin "2") (pinfunction "2_2") (pintype "passive"))
      (node (ref "C18") (pin "1") (pinfunction "1_1") (pintype "passive"))
      (node (ref "R17") (pin "2") (pinfunction "2_2") (pintype "passive"))
    )
    (net (code "68") (name "/SCK") (class "Default")
      (node (ref "P4") (pin "9") (pinfunction "9_9") (pintype "passive"))
      (node (ref "R21") (pin "1") (pinfunction "1_1") (pintype "passive"))
      (node (ref "U1") (pin "24") (pinfunction "EMUC3/SCK1/RF6_24") (pintype "bidirectional"))
    )
    (net (code "69") (name "/SCLK3V") (class "Default")
      (node (ref "J10") (pin "5") (pinfunction "CLK_5") (pintype "bidirectional"))
      (node (ref "R21") (pin "2") (pinfunction "2_2") (pintype "passive"))
      (node (ref "R25") (pin "2") (pinfunction "2_2") (pintype "passive"))
    )
    (net (code "70") (name "/SDETECT") (class "Default")
      (node (ref "J10") (pin "SWB") (pinfunction "B_SWB") (pintype "bidirectional"))
      (node (ref "R31") (pin "1") (pinfunction "1_1") (pintype "passive"))
      (node (ref "W6") (pin "1") (pinfunction "C1_1") (pintype "passive"))
    )
    (net (code "71") (name "/SDI") (class "Default")
      (node (ref "J10") (pin "3") (pinfunction "CMD/DI_3") (pintype "bidirectional"))
      (node (ref "P4") (pin "5") (pinfunction "5_5") (pintype "passive"))
      (node (ref "U1") (pin "26") (pinfunction "U1RX/SDI1/SDA/RF2_26") (pintype "bidirectional"))
    )
    (net (code "72") (name "/SDIN") (class "Default")
      (node (ref "P3") (pin "6") (pinfunction "6_6") (pintype "passive"))
      (node (ref "U4") (pin "13") (pinfunction "DX0_13") (pintype "tri_state"))
    )
    (net (code "73") (name "/SDO") (class "Default")
      (node (ref "P4") (pin "7") (pinfunction "7_7") (pintype "passive"))
      (node (ref "R18") (pin "1") (pinfunction "1_1") (pintype "passive"))
      (node (ref "U1") (pin "25") (pinfunction "EMUD3/U1TX/SDO1/SCL/RF3_25") (pintype "bidirectional"))
    )
    (net (code "74") (name "/SDO3V") (class "Default")
      (node (ref "J10") (pin "7") (pinfunction "DATA0/DO_7") (pintype "bidirectional"))
      (node (ref "R18") (pin "2") (pinfunction "2_2") (pintype "passive"))
      (node (ref "R26") (pin "2") (pinfunction "2_2") (pintype "passive"))
    )
    (net (code "75") (name "/SDOUT") (class "Default")
      (node (ref "P3") (pin "8") (pinfunction "8_8") (pintype "passive"))
      (node (ref "U4") (pin "7") (pinfunction "DR0_7") (pintype "input"))
    )
    (net (code "76") (name "/SE_BTL_N") (class "Default")
      (node (ref "R27") (pin "2") (pinfunction "2_2") (pintype "passive"))
      (node (ref "U2") (pin "19") (pinfunction "SE/*BTL_19") (pintype "input"))
    )
    (net (code "77") (name "/TXD") (class "Default")
      (node (ref "U1") (pin "16") (pinfunction "EMUC1/SOSCO/T1CK/U1ARX/CN0/RC14_16") (pintype "bidirectional"))
      (node (ref "W5") (pin "2") (pinfunction "C2_2") (pintype "passive"))
    )
    (net (code "78") (name "/TXD1") (class "Default")
      (node (ref "U6") (pin "12") (pinfunction "ROUT1_12") (pintype "output"))
      (node (ref "W5") (pin "1") (pinfunction "C1_1") (pintype "passive"))
    )
    (net (code "79") (name "/TXD1HV") (class "Default")
      (node (ref "J8") (pin "2") (pinfunction "2_2") (pintype "passive"))
      (node (ref "U6") (pin "13") (pinfunction "RIN1_13") (pintype "input"))
    )
    (net (code "80") (name "/TXD2HV") (class "Default")
      (node (ref "J7") (pin "2") (pinfunction "2_2") (pintype "passive"))
      (node (ref "U6") (pin "8") (pinfunction "RIN2_8") (pintype "input"))
    )
    (net (code "81") (name "/VAC8V7") (class "Default")
      (node (ref "D1") (pin "2") (pinfunction "K_2") (pintype "passive"))
      (node (ref "D2") (pin "2") (pinfunction "K_2") (pintype "passive"))
      (node (ref "D3") (pin "1") (pinfunction "A_1") (pintype "passive"))
      (node (ref "D5") (pin "2") (pinfunction "AC_2") (pintype "passive"))
      (node (ref "J9") (pin "2") (pinfunction "2_2") (pintype "power_in"))
      (node (ref "J9") (pin "2A") (pinfunction "2A_2A") (pintype "power_in"))
      (node (ref "J9") (pin "2B") (pinfunction "2B_2B") (pintype "power_in"))
    )
    (net (code "82") (name "/VAC9V0_1") (class "Default")
      (node (ref "D1") (pin "1") (pinfunction "A_1") (pintype "passive"))
    )
    (net (code "83") (name "/VAC9V0_2") (class "Default")
      (node (ref "D2") (pin "1") (pinfunction "A_1") (pintype "passive"))
    )
    (net (code "84") (name "/VCODEC_N") (class "Default")
      (node (ref "C35") (pin "1") (pinfunction "1_1") (pintype "passive"))
      (node (ref "U3") (pin "5") (pinfunction "-VO_5") (pintype "power_in"))
      (node (ref "U4") (pin "3") (pinfunction "VBB_3") (pintype "power_in"))
    )
    (net (code "85") (name "/VCODEC_P") (class "Default")
      (node (ref "C36") (pin "1") (pinfunction "1_1") (pintype "passive"))
      (node (ref "P3") (pin "2") (pinfunction "2_2") (pintype "passive"))
      (node (ref "R8") (pin "1") (pinfunction "1_1") (pintype "passive"))
      (node (ref "U3") (pin "1") (pinfunction "+VI_1") (pintype "power_in"))
      (node (ref "U4") (pin "19") (pinfunction "VCC_19") (pintype "power_in"))
    )
    (net (code "86") (name "/VDD4V7A") (class "Default")
      (node (ref "C14") (pin "1") (pinfunction "1_1") (pintype "passive"))
      (node (ref "C15") (pin "1") (pinfunction "1_1") (pintype "passive"))
      (node (ref "C19") (pin "1") (pinfunction "1_1") (pintype "passive"))
      (node (ref "C23") (pin "1") (pinfunction "1_1") (pintype "passive"))
      (node (ref "C24") (pin "1") (pinfunction "1_1") (pintype "passive"))
      (node (ref "C25") (pin "1") (pinfunction "1_1") (pintype "passive"))
      (node (ref "C3") (pin "1") (pinfunction "1_1") (pintype "passive"))
      (node (ref "C6") (pin "1") (pinfunction "1_1") (pintype "passive"))
      (node (ref "D4") (pin "1") (pinfunction "A_1") (pintype "passive"))
      (node (ref "J10") (pin "4") (pinfunction "VCC_4") (pintype "power_in"))
      (node (ref "J5") (pin "1") (pinfunction "V_BUS_1") (pintype "passive"))
      (node (ref "P3") (pin "1") (pinfunction "1_1") (pintype "passive"))
      (node (ref "R19") (pin "1") (pinfunction "TOP_1") (pintype "passive"))
      (node (ref "R20") (pin "2") (pinfunction "2_2") (pintype "passive"))
      (node (ref "R3") (pin "1") (pinfunction "1_1") (pintype "passive"))
      (node (ref "U1") (pin "40") (pinfunction "AVDD_40") (pintype "power_in"))
      (node (ref "U2") (pin "3") (pinfunction "PVDD_3") (pintype "power_in"))
      (node (ref "U2") (pin "6") (pinfunction "VDD_6") (pintype "power_in"))
      (node (ref "U2") (pin "9") (pinfunction "PVDD_9") (pintype "power_in"))
      (node (ref "U5") (pin "5") (pinfunction "VO_5") (pintype "power_in"))
      (node (ref "U6") (pin "16") (pinfunction "VCC_16") (pintype "power_in"))
    )
    (net (code "87") (name "/VDD5V0") (class "Default")
      (node (ref "C10") (pin "1") (pinfunction "1_1") (pintype "passive"))
      (node (ref "C12") (pin "1") (pinfunction "1_1") (pintype "passive"))
      (node (ref "C4") (pin "1") (pinfunction "1_1") (pintype "passive"))
      (node (ref "C7") (pin "1") (pinfunction "1_1") (pintype "passive"))
      (node (ref "C8") (pin "1") (pinfunction "1_1") (pintype "passive"))
      (node (ref "C9") (pin "1") (pinfunction "1_1") (pintype "passive"))
      (node (ref "D4") (pin "2") (pinfunction "K_2") (pintype "passive"))
      (node (ref "J10") (pin "SWA") (pinfunction "A_SWA") (pintype "bidirectional"))
      (node (ref "P1") (pin "2") (pinfunction "2_2") (pintype "passive"))
      (node (ref "R1") (pin "2") (pinfunction "2_2") (pintype "passive"))
      (node (ref "R14") (pin "2") (pinfunction "2_2") (pintype "passive"))
      (node (ref "R7") (pin "2") (pinfunction "2_2") (pintype "passive"))
      (node (ref "U1") (pin "11") (pinfunction "VDD_11") (pintype "power_in"))
      (node (ref "U1") (pin "21") (pinfunction "VDD_21") (pintype "power_in"))
      (node (ref "U1") (pin "32") (pinfunction "VDD_32") (pintype "power_in"))
    )
    (net (code "88") (name "/VDD8V3") (class "Default")
      (node (ref "C5") (pin "1") (pinfunction "1_1") (pintype "passive"))
      (node (ref "D3") (pin "2") (pinfunction "K_2") (pintype "passive"))
      (node (ref "D5") (pin "1") (pinfunction "V+_1") (pintype "passive"))
      (node (ref "U5") (pin "2") (pinfunction "VI_2") (pintype "power_in"))
    )
    (net (code "89") (name "/VS_N") (class "Default")
      (node (ref "C33") (pin "1") (pinfunction "1_1") (pintype "passive"))
      (node (ref "U6") (pin "6") (pinfunction "VS-_6") (pintype "power_in"))
    )
    (net (code "90") (name "/VS_P") (class "Default")
      (node (ref "C34") (pin "1") (pinfunction "1_1") (pintype "passive"))
      (node (ref "U6") (pin "2") (pinfunction "VS+_2") (pintype "power_in"))
    )
    (net (code "91") (name "AGND") (class "Default")
      (node (ref "C19") (pin "2") (pinfunction "2_2") (pintype "passive"))
      (node (ref "C22") (pin "2") (pinfunction "2_2") (pintype "passive"))
      (node (ref "C23") (pin "2") (pinfunction "2_2") (pintype "passive"))
      (node (ref "C24") (pin "2") (pinfunction "2_2") (pintype "passive"))
      (node (ref "C25") (pin "2") (pinfunction "2_2") (pintype "passive"))
      (node (ref "C33") (pin "2") (pinfunction "2_2") (pintype "passive"))
      (node (ref "C34") (pin "2") (pinfunction "2_2") (pintype "passive"))
      (node (ref "C35") (pin "2") (pinfunction "2_2") (pintype "passive"))
      (node (ref "C36") (pin "2") (pinfunction "2_2") (pintype "passive"))
      (node (ref "C6") (pin "2") (pinfunction "2_2") (pintype "passive"))
      (node (ref "J1") (pin "1A") (pinfunction "Ground_1A") (pintype "power_in"))
      (node (ref "J11") (pin "1A") (pinfunction "Ground_1A") (pintype "power_in"))
      (node (ref "J2") (pin "1A") (pinfunction "Ground_1A") (pintype "power_in"))
      (node (ref "J3") (pin "1A") (pinfunction "Ground_1A") (pintype "power_in"))
      (node (ref "J4") (pin "1A") (pinfunction "Ground_1A") (pintype "power_in"))
      (node (ref "J6") (pin "1") (pinfunction "1_1") (pintype "passive"))
      (node (ref "J6") (pin "1A") (pinfunction "1A_1A") (pintype "passive"))
      (node (ref "J6") (pin "1B") (pinfunction "1B_1B") (pintype "passive"))
      (node (ref "J7") (pin "1") (pinfunction "1_1") (pintype "passive"))
      (node (ref "J7") (pin "10") (pinfunction "MH1_10") (pintype "passive"))
      (node (ref "J7") (pin "11") (pinfunction "MH2_11") (pintype "passive"))
      (node (ref "J8") (pin "1") (pinfunction "1_1") (pintype "passive"))
      (node (ref "J8") (pin "10") (pinfunction "MH1_10") (pintype "passive"))
      (node (ref "J8") (pin "11") (pinfunction "MH2_11") (pintype "passive"))
      (node (ref "P3") (pin "12") (pinfunction "12_12") (pintype "passive"))
      (node (ref "R19") (pin "2") (pinfunction "BOT_2") (pintype "passive"))
      (node (ref "R22") (pin "1") (pinfunction "1_1") (pintype "passive"))
      (node (ref "R29") (pin "1") (pinfunction "1_1") (pintype "passive"))
      (node (ref "R4") (pin "2") (pinfunction "2_2") (pintype "passive"))
      (node (ref "R9") (pin "2") (pinfunction "2_2") (pintype "passive"))
      (node (ref "U1") (pin "39") (pinfunction "AVSS_39") (pintype "power_in"))
      (node (ref "U2") (pin "1") (pinfunction "PGND_1") (pintype "power_in"))
      (node (ref "U2") (pin "11") (pinfunction "PGND_11") (pintype "power_in"))
      (node (ref "U2") (pin "15") (pinfunction "*FADE_15") (pintype "input"))
      (node (ref "U2") (pin "17") (pinfunction "AGND_17") (pintype "power_in"))
      (node (ref "U3") (pin "2") (pinfunction "-VI_2") (pintype "power_in"))
      (node (ref "U3") (pin "7") (pinfunction "+VO_7") (pintype "power_in"))
      (node (ref "U4") (pin "1") (pinfunction "GND_1") (pintype "power_in"))
      (node (ref "U6") (pin "15") (pinfunction "GND_15") (pintype "power_in"))
      (node (ref "W3") (pin "2") (pinfunction "C2_2") (pintype "passive"))
    )
    (net (code "92") (name "DGND") (class "Default")
      (node (ref "C1") (pin "1") (pinfunction "1_1") (pintype "passive"))
      (node (ref "C10") (pin "2") (pinfunction "2_2") (pintype "passive"))
      (node (ref "C12") (pin "2") (pinfunction "2_2") (pintype "passive"))
      (node (ref "C13") (pin "2") (pinfunction "2_2") (pintype "passive"))
      (node (ref "C14") (pin "2") (pinfunction "2_2") (pintype "passive"))
      (node (ref "C15") (pin "2") (pinfunction "2_2") (pintype "passive"))
      (node (ref "C18") (pin "2") (pinfunction "2_2") (pintype "passive"))
      (node (ref "C2") (pin "1") (pinfunction "1_1") (pintype "passive"))
      (node (ref "C21") (pin "2") (pinfunction "2_2") (pintype "passive"))
      (node (ref "C27") (pin "2") (pinfunction "2_2") (pintype "passive"))
      (node (ref "C3") (pin "2") (pinfunction "2_2") (pintype "passive"))
      (node (ref "C30") (pin "2") (pinfunction "2_2") (pintype "passive"))
      (node (ref "C4") (pin "2") (pinfunction "2_2") (pintype "passive"))
      (node (ref "C5") (pin "2") (pinfunction "2_2") (pintype "passive"))
      (node (ref "C7") (pin "2") (pinfunction "2_2") (pintype "passive"))
      (node (ref "C8") (pin "2") (pinfunction "2_2") (pintype "passive"))
      (node (ref "C9") (pin "2") (pinfunction "2_2") (pintype "passive"))
      (node (ref "D5") (pin "3") (pinfunction "V-_3") (pintype "passive"))
      (node (ref "D5") (pin "4") (pinfunction "AC_4") (pintype "passive"))
      (node (ref "J10") (pin "6") (pinfunction "GND_6") (pintype "power_in"))
      (node (ref "J5") (pin "5") (pinfunction "GND_5") (pintype "passive"))
      (node (ref "J5") (pin "6") (pinfunction "MH1_6") (pintype "passive"))
      (node (ref "J5") (pin "7") (pinfunction "MH2_7") (pintype "passive"))
      (node (ref "J9") (pin "1") (pinfunction "1_1") (pintype "power_in"))
      (node (ref "J9") (pin "1A") (pinfunction "1A_1A") (pintype "power_in"))
      (node (ref "J9") (pin "1B") (pinfunction "1B_1B") (pintype "power_in"))
      (node (ref "J9") (pin "3") (pinfunction "3_3") (pintype "power_in"))
      (node (ref "J9") (pin "3A") (pinfunction "3A_3A") (pintype "power_in"))
      (node (ref "J9") (pin "3B") (pinfunction "3B_3B") (pintype "power_in"))
      (node (ref "P1") (pin "3") (pinfunction "3_3") (pintype "passive"))
      (node (ref "P3") (pin "11") (pinfunction "11_11") (pintype "passive"))
      (node (ref "R24") (pin "1") (pinfunction "1_1") (pintype "passive"))
      (node (ref "R25") (pin "1") (pinfunction "1_1") (pintype "passive"))
      (node (ref "R26") (pin "1") (pinfunction "1_1") (pintype "passive"))
      (node (ref "R31") (pin "2") (pinfunction "2_2") (pintype "passive"))
      (node (ref "R5") (pin "1") (pinfunction "1_1") (pintype "passive"))
      (node (ref "S0") (pin "1") (pinfunction "COMMON_1") (pintype "passive"))
      (node (ref "S1") (pin "1") (pinfunction "COMMON_1") (pintype "passive"))
      (node (ref "S2") (pin "1") (pinfunction "COMMON_1") (pintype "passive"))
      (node (ref "U1") (pin "12") (pinfunction "VSS_12") (pintype "power_in"))
      (node (ref "U1") (pin "20") (pinfunction "VSS_20") (pintype "power_in"))
      (node (ref "U1") (pin "31") (pinfunction "VSS_31") (pintype "power_in"))
      (node (ref "U5") (pin "1") (pinfunction "GND_1") (pintype "power_in"))
      (node (ref "W3") (pin "1") (pinfunction "C1_1") (pintype "passive"))
    )
    (net (code "93") (name "Net-(J11-Signal)") (class "Default")
      (node (ref "C11") (pin "1") (pinfunction "1_1") (pintype "passive"))
      (node (ref "J11") (pin "2B") (pinfunction "Signal_2B") (pintype "input"))
    )
    (net (code "94") (name "unconnected-(J5-D+-Pad3)") (class "Default")
      (node (ref "J5") (pin "3") (pinfunction "D+_3") (pintype "passive"))
    )
    (net (code "95") (name "unconnected-(J5-D--Pad2)") (class "Default")
      (node (ref "J5") (pin "2") (pinfunction "D-_2") (pintype "passive"))
    )
    (net (code "96") (name "unconnected-(J5-ID-Pad4)") (class "Default")
      (node (ref "J5") (pin "4") (pinfunction "ID_4") (pintype "passive"))
    )
    (net (code "97") (name "unconnected-(J7-Pad4)") (class "Default")
      (node (ref "J7") (pin "4") (pinfunction "4_4") (pintype "passive"))
    )
    (net (code "98") (name "unconnected-(J7-Pad5)") (class "Default")
      (node (ref "J7") (pin "5") (pinfunction "5_5") (pintype "passive"))
    )
    (net (code "99") (name "unconnected-(J7-Pad6)") (class "Default")
      (node (ref "J7") (pin "6") (pinfunction "6_6") (pintype "passive"))
    )
    (net (code "100") (name "unconnected-(J7-Pad7)") (class "Default")
      (node (ref "J7") (pin "7") (pinfunction "7_7") (pintype "passive"))
    )
    (net (code "101") (name "unconnected-(J7-Pad8)") (class "Default")
      (node (ref "J7") (pin "8") (pinfunction "8_8") (pintype "passive"))
    )
    (net (code "102") (name "unconnected-(J7-Pad9)") (class "Default")
      (node (ref "J7") (pin "9") (pinfunction "9_9") (pintype "passive"))
    )
    (net (code "103") (name "unconnected-(J8-Pad4)") (class "Default")
      (node (ref "J8") (pin "4") (pinfunction "4_4") (pintype "passive"))
    )
    (net (code "104") (name "unconnected-(J8-Pad5)") (class "Default")
      (node (ref "J8") (pin "5") (pinfunction "5_5") (pintype "passive"))
    )
    (net (code "105") (name "unconnected-(J8-Pad6)") (class "Default")
      (node (ref "J8") (pin "6") (pinfunction "6_6") (pintype "passive"))
    )
    (net (code "106") (name "unconnected-(J8-Pad7)") (class "Default")
      (node (ref "J8") (pin "7") (pinfunction "7_7") (pintype "passive"))
    )
    (net (code "107") (name "unconnected-(J8-Pad8)") (class "Default")
      (node (ref "J8") (pin "8") (pinfunction "8_8") (pintype "passive"))
    )
    (net (code "108") (name "unconnected-(J8-Pad9)") (class "Default")
      (node (ref "J8") (pin "9") (pinfunction "9_9") (pintype "passive"))
    )
    (net (code "109") (name "unconnected-(J10-DATA1-Pad8)") (class "Default")
      (node (ref "J10") (pin "8") (pinfunction "DATA1_8") (pintype "bidirectional"))
    )
    (net (code "110") (name "unconnected-(J10-DATA2-Pad1)") (class "Default")
      (node (ref "J10") (pin "1") (pinfunction "DATA2_1") (pintype "bidirectional"))
    )
    (net (code "111") (name "unconnected-(P1-Pad6)") (class "Default")
      (node (ref "P1") (pin "6") (pinfunction "6_6") (pintype "passive+no_connect"))
    )
    (net (code "112") (name "unconnected-(U1-AN0{slash}VREF+{slash}CN2{slash}RB0-Pad2)") (class "Default")
      (node (ref "U1") (pin "2") (pinfunction "AN0/VREF+/CN2/RB0_2") (pintype "bidirectional"))
    )
    (net (code "113") (name "unconnected-(U1-AN1{slash}VREF-{slash}CN3{slash}RB1-Pad3)") (class "Default")
      (node (ref "U1") (pin "3") (pinfunction "AN1/VREF-/CN3/RB1_3") (pintype "bidirectional"))
    )
    (net (code "114") (name "unconnected-(U1-AN2{slash}~{SS1}{slash}LVDIN{slash}CN4{slash}RB2-Pad4)") (class "Default")
      (node (ref "U1") (pin "4") (pinfunction "AN2/~{SS1}/LVDIN/CN4/RB2_4") (pintype "bidirectional"))
    )
    (net (code "115") (name "unconnected-(U1-AN3{slash}CN5{slash}RB3-Pad5)") (class "Default")
      (node (ref "U1") (pin "5") (pinfunction "AN3/CN5/RB3_5") (pintype "bidirectional"))
    )
    (net (code "116") (name "unconnected-(U1-AN4{slash}IC7{slash}CN6{slash}RB4-Pad6)") (class "Default")
      (node (ref "U1") (pin "6") (pinfunction "AN4/IC7/CN6/RB4_6") (pintype "bidirectional"))
    )
    (net (code "117") (name "unconnected-(U1-AN5{slash}IC8{slash}CN7{slash}RB5-Pad7)") (class "Default")
      (node (ref "U1") (pin "7") (pinfunction "AN5/IC8/CN7/RB5_7") (pintype "bidirectional"))
    )
    (net (code "118") (name "unconnected-(U1-PGC{slash}EMUC{slash}AN6{slash}OCFA{slash}RB6-Pad8)") (class "Default")
      (node (ref "U1") (pin "8") (pinfunction "PGC/EMUC/AN6/OCFA/RB6_8") (pintype "bidirectional"))
    )
    (net (code "119") (name "unconnected-(U1-PGD{slash}EMUD{slash}AN7{slash}RB7-Pad9)") (class "Default")
      (node (ref "U1") (pin "9") (pinfunction "PGD/EMUD/AN7/RB7_9") (pintype "bidirectional"))
    )
    (net (code "120") (name "unconnected-(U2-NC-Pad13)") (class "Default")
      (node (ref "U2") (pin "13") (pinfunction "NC_13") (pintype "passive+no_connect"))
    )
    (net (code "121") (name "unconnected-(U4-IL0-Pad18)") (class "Default")
      (node (ref "U4") (pin "18") (pinfunction "IL0_18") (pintype "bidirectional+no_connect"))
    )
    (net (code "122") (name "unconnected-(U4-IL1-Pad17)") (class "Default")
      (node (ref "U4") (pin "17") (pinfunction "IL1_17") (pintype "bidirectional+no_connect"))
    )
    (net (code "123") (name "unconnected-(U4-IL2-Pad5)") (class "Default")
      (node (ref "U4") (pin "5") (pinfunction "IL2_5") (pintype "bidirectional+no_connect"))
    )
    (net (code "124") (name "unconnected-(U4-IL3-Pad4)") (class "Default")
      (node (ref "U4") (pin "4") (pinfunction "IL3_4") (pintype "bidirectional+no_connect"))
    )
    (net (code "125") (name "unconnected-(U4-IL4-Pad16)") (class "Default")
      (node (ref "U4") (pin "16") (pinfunction "IL4_16") (pintype "bidirectional+no_connect"))
    )
    (net (code "126") (name "unconnected-(U4-~{TSX}0-Pad14)") (class "Default")
      (node (ref "U4") (pin "14") (pinfunction "~{TSX}0_14") (pintype "open_collector+no_connect"))
    )
  )
)
